# Balanced_Car.net
KiCad netlist of a schematic drawn in EasyEDA Pro
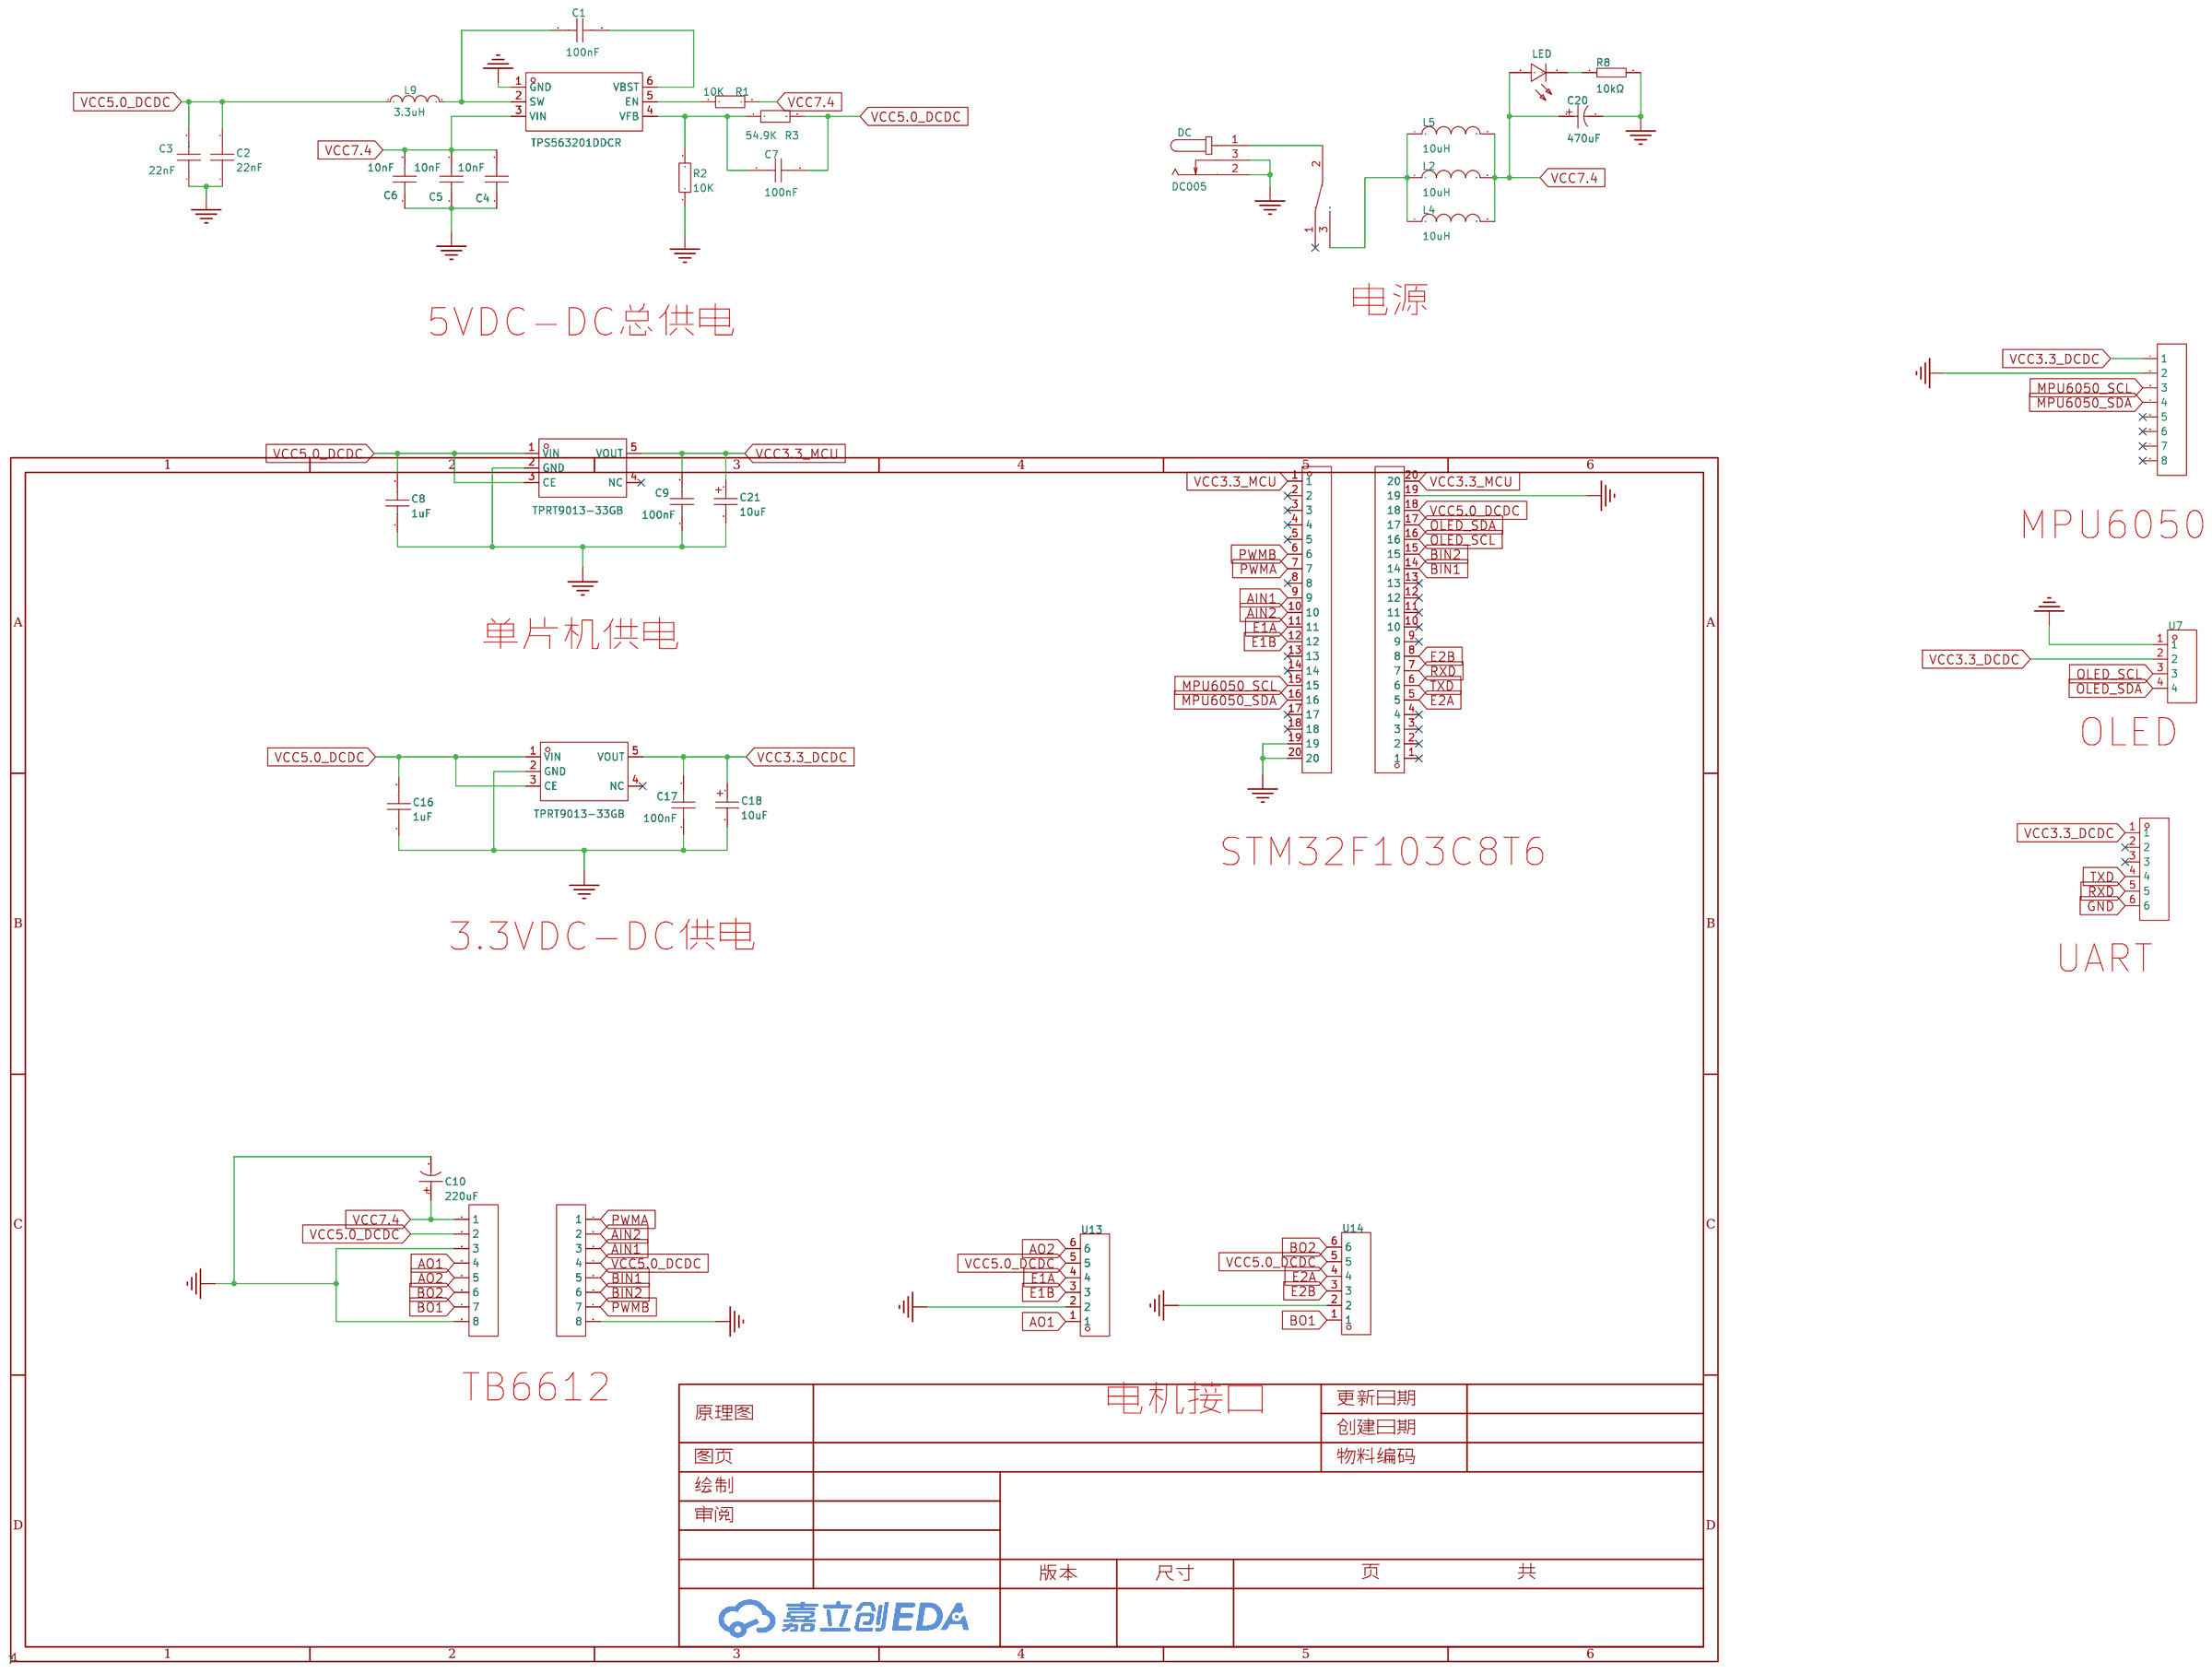
[diagram p0: schematic sheet]

(export (version "E")
  (design (tool "Eeschema 10.0.6"))
  (components
    (comp (ref "C1")
      (value "100nF")
      (footprint "easyedapro:C0603")
      (libsource (lib "easyedapro") (part "capacitance"))
    )
    (comp (ref "C2")
      (value "22nF")
      (footprint "easyedapro:C0603")
      (libsource (lib "easyedapro") (part "capacitance"))
    )
    (comp (ref "C3")
      (value "22nF")
      (footprint "easyedapro:C0603")
      (libsource (lib "easyedapro") (part "capacitance"))
    )
    (comp (ref "C4")
      (value "10nF")
      (footprint "easyedapro:C0603")
      (libsource (lib "easyedapro") (part "capacitance"))
    )
    (comp (ref "C5")
      (value "10nF")
      (footprint "easyedapro:C0603")
      (libsource (lib "easyedapro") (part "capacitance"))
    )
    (comp (ref "C6")
      (value "10nF")
      (footprint "easyedapro:C0603")
      (libsource (lib "easyedapro") (part "capacitance"))
    )
    (comp (ref "C7")
      (value "100nF")
      (footprint "easyedapro:C0603")
      (libsource (lib "easyedapro") (part "capacitance"))
    )
    (comp (ref "C8")
      (value "1uF")
      (footprint "easyedapro:C0603")
      (libsource (lib "easyedapro") (part "capacitance"))
    )
    (comp (ref "C9")
      (value "100nF")
      (footprint "easyedapro:C0603")
      (libsource (lib "easyedapro") (part "capacitance"))
    )
    (comp (ref "C10")
      (value "220uF")
      (footprint "easyedapro:CAP-TH_BD6.3-P2.50-D1.0-FD")
      (description "容值:220uF;精度:±20%;额定电压:16V;纹波电流:-;等效串联电阻:-;")
      (fields
        (field (name "Manufacturer Part") "KS227M016E07RR0VH2FP0")
        (field (name "Manufacturer") "CX(承兴)")
      )
      (libsource (lib "easyedapro") (part "220uF 16V 6.3*7"))
    )
    (comp (ref "C16")
      (value "1uF")
      (footprint "easyedapro:C0603")
      (libsource (lib "easyedapro") (part "capacitance"))
    )
    (comp (ref "C17")
      (value "100nF")
      (footprint "easyedapro:C0603")
      (libsource (lib "easyedapro") (part "capacitance"))
    )
    (comp (ref "C18")
      (value "10uF")
      (footprint "easyedapro:CAP-SMD_L3.2-W1.6-RD-C7171")
      (description "容值:10uF;精度:±10%;额定电压:16V;等效串联电阻:3Ω@100kHz;")
      (fields (field (name "Manufacturer Part") "TAJA106K016RNJ") (field (name "Manufacturer") "Kyocera AVX"))
      (libsource (lib "easyedapro") (part "TAJA106K016RNJ"))
    )
    (comp (ref "C20")
      (value "470uF")
      (footprint "easyedapro:CAP-TH_BD8.0-P3.50-D0.6-FD")
      (description "容值:470uF;精度:±20%;额定电压:25V;")
      (fields
        (field (name "Manufacturer Part") "KM477M025F12RR0VH2FP0")
        (field (name "Manufacturer") "CX(承兴)")
      )
      (libsource (lib "easyedapro") (part "470uF 25V 8*12"))
    )
    (comp (ref "C21")
      (value "10uF")
      (footprint "easyedapro:CAP-SMD_L3.2-W1.6-RD-C7171")
      (description "容值:10uF;精度:±10%;额定电压:16V;等效串联电阻:3Ω@100kHz;")
      (fields (field (name "Manufacturer Part") "TAJA106K016RNJ") (field (name "Manufacturer") "Kyocera AVX"))
      (libsource (lib "easyedapro") (part "TAJA106K016RNJ"))
    )
    (comp (ref "DC")
      (value "DC005")
      (footprint "easyedapro:DC-IN-TH_DC005")
      (description "连接器类型:DC电源插座;安装方式:弯插;触点内径:2mm;触点外径:6.3mm;额定电流:500mA;额定电压:30V;工作温度范围:-40°C~+55°C;")
      (fields (field (name "Manufacturer") "SHOU HAN(首韩)"))
      (libsource (lib "easyedapro") (part "DC005_C431533"))
    )
    (comp (ref "H7")
      (value "~")
      (footprint "easyedapro:HDR-TH_8P-P2.54-V-F-1")
      (libsource (lib "easyedapro") (part "Header-Female-2.54_1x8"))
    )
    (comp (ref "H8")
      (value "PM254V-11-06-H85")
      (footprint "easyedapro:HDR-TH_6P-P2.54-V-F")
      (fields (field (name "Manufacturer") "XFCN(兴飞)"))
      (libsource (lib "easyedapro") (part "PM254V-11-06-H85"))
    )
    (comp (ref "L2")
      (value "10uH")
      (fields
        (field (name "Manufacturer Part") "MGFL2012F100MT-LF")
        (field (name "Manufacturer") "microgate(麦捷科技)")
      )
      (libsource (lib "easyedapro") (part "IND"))
    )
    (comp (ref "L4")
      (value "10uH")
      (fields
        (field (name "Manufacturer Part") "MGFL2012F100MT-LF")
        (field (name "Manufacturer") "microgate(麦捷科技)")
      )
      (libsource (lib "easyedapro") (part "IND"))
    )
    (comp (ref "L5")
      (value "10uH")
      (fields
        (field (name "Manufacturer Part") "MGFL2012F100MT-LF")
        (field (name "Manufacturer") "microgate(麦捷科技)")
      )
      (libsource (lib "easyedapro") (part "IND"))
    )
    (comp (ref "L9")
      (value "3.3uH")
      (footprint "easyedapro:IND-SMD_L7.0-W6.6")
      (description "电感值:3.3uH;精度:±20%;额定电流:8.5A;饱和电流(Isat):9.5A;类型:一体成型电感;")
      (fields (field (name "Manufacturer Part") "FXL0630-3R3-M") (field (name "Manufacturer") "cjiang(长江微电)"))
      (libsource (lib "easyedapro") (part "FXL0630-3R3-M"))
    )
    (comp (ref "LED")
      (value "NCD0603G1")
      (footprint "easyedapro:LED0603-RD")
      (fields (field (name "Manufacturer") "国星光电"))
      (libsource (lib "easyedapro") (part "FC-D1608UGK-520D10"))
    )
    (comp (ref "R1") (value "10K") (footprint "easyedapro:R0603") (libsource (lib "easyedapro") (part "电阻")))
    (comp (ref "R2") (value "10K") (footprint "easyedapro:R0603") (libsource (lib "easyedapro") (part "电阻")))
    (comp (ref "R3")
      (value "54.9K")
      (footprint "easyedapro:R0603")
      (libsource (lib "easyedapro") (part "电阻"))
    )
    (comp (ref "R8")
      (value "10kΩ")
      (fields
        (field (name "Manufacturer Part") "0805W8F1501T5E")
        (field (name "Manufacturer") "UNI-ROYAL(厚声)")
      )
      (libsource (lib "easyedapro") (part "RES"))
    )
    (comp (ref "U1")
      (value "TPS563201DDCR")
      (footprint "easyedapro:SOT-23-6_L2.9-W1.6-P0.95-LS2.8-BR")
      (description "功能类型:降压型;输出类型:可调;输入电压:4.5V~17V;输出电压:768mV~7V;输出电流:3A;")
      (fields (field (name "Manufacturer") "TI(德州仪器)"))
      (libsource (lib "easyedapro") (part "TPS563201DDCR"))
    )
    (comp (ref "U2")
      (value "~")
      (footprint "easyedapro:HDR-TH_8P-P2.54-V-F-1")
      (libsource (lib "easyedapro") (part "Header-Female-2.54_1x8"))
    )
    (comp (ref "U3")
      (value "TPRT9013-33GB")
      (footprint "easyedapro:SOT-23-5_L3.0-W1.7-P0.95-LS2.8-BL")
      (description "输出类型:-;")
      (fields (field (name "Manufacturer") "TECH PUBLIC(台舟)"))
      (libsource (lib "easyedapro") (part "TPRT9013-33GB"))
    )
    (comp (ref "U5")
      (value "~")
      (footprint "easyedapro:HDR-TH_8P-P2.54-V-F-1")
      (libsource (lib "easyedapro") (part "Header-Female-2.54_1x8"))
    )
    (comp (ref "U6")
      (value "TPRT9013-33GB")
      (footprint "easyedapro:SOT-23-5_L3.0-W1.7-P0.95-LS2.8-BL")
      (description "输出类型:-;")
      (fields (field (name "Manufacturer") "TECH PUBLIC(台舟)"))
      (libsource (lib "easyedapro") (part "TPRT9013-33GB"))
    )
    (comp (ref "U7")
      (value "PM2.54-1*4")
      (footprint "easyedapro:HDR-TH_4P-P2.54-V-F")
      (fields (field (name "Manufacturer") "ZHOURI(洲日)"))
      (libsource (lib "easyedapro") (part "PM2.54-1*4"))
    )
    (comp (ref "U11")
      (value "KH-2.54FH-1X20P-H8.5")
      (footprint "easyedapro:HDR-TH_20P-P2.54-V-F-2")
      (fields (field (name "Manufacturer") "kinghelm(金航标)"))
      (libsource (lib "easyedapro") (part "KH-2.54FH-1X20P-H8.5"))
    )
    (comp (ref "U12")
      (value "KH-2.54FH-1X20P-H8.5")
      (footprint "easyedapro:HDR-TH_20P-P2.54-V-F-2")
      (fields (field (name "Manufacturer") "kinghelm(金航标)"))
      (libsource (lib "easyedapro") (part "KH-2.54FH-1X20P-H8.5"))
    )
    (comp (ref "U13")
      (value "X8821WR-06S-N0SN")
      (footprint "easyedapro:CONN-TH_6P-P2.50_X8821WR-06S-N2SN")
      (description "插针结构:1x6P;间距:2.5mm;安装方式:弯插;参考系列:XH;总PIN数:6P;排数:1;每排PIN数:6;行距:-;额定电流:3A;触头材质:黄铜;触头镀层:锡;工作温度范围:-;")
      (fields (field (name "Manufacturer") "XKB Connection(中国星坤)"))
      (libsource (lib "easyedapro") (part "X8821WR-06S-N0SN"))
    )
    (comp (ref "U14")
      (value "X8821WR-06S-N0SN")
      (footprint "easyedapro:CONN-TH_6P-P2.50_X8821WR-06S-N2SN")
      (description "插针结构:1x6P;间距:2.5mm;安装方式:弯插;参考系列:XH;总PIN数:6P;排数:1;每排PIN数:6;行距:-;额定电流:3A;触头材质:黄铜;触头镀层:锡;工作温度范围:-;")
      (fields (field (name "Manufacturer") "XKB Connection(中国星坤)"))
      (libsource (lib "easyedapro") (part "X8821WR-06S-N0SN"))
    )
    (comp (ref "U16")
      (value "MT-0-102-A101-M200-RS")
      (footprint "easyedapro:SW-TH_MT-0-103-A101-M200-RS")
      (description "电路结构:单刀双掷;机械寿命:-;额定电流:5A;额定电压(AC):125V;安装方式:直插;")
      (fields (field (name "Manufacturer") "YUEN FUNG(源丰)"))
      (libsource (lib "easyedapro") (part "MT-0-102-A101-M200-RS+PJ"))
    )
  )
  (nets
    (net (code "1") (name "AIN1") (class "Default")
      (node (ref "U11") (pin "9") (pinfunction "9_9") (pintype "unspecified"))
      (node (ref "U2") (pin "3") (pinfunction "3_3") (pintype "input"))
    )
    (net (code "2") (name "AIN2") (class "Default")
      (node (ref "U11") (pin "10") (pinfunction "10_10") (pintype "unspecified"))
      (node (ref "U2") (pin "2") (pinfunction "2_2") (pintype "input"))
    )
    (net (code "3") (name "AO1") (class "Default")
      (node (ref "U13") (pin "1") (pinfunction "1_1") (pintype "unspecified"))
      (node (ref "U5") (pin "4") (pinfunction "4_4") (pintype "input"))
    )
    (net (code "4") (name "AO2") (class "Default")
      (node (ref "U13") (pin "6") (pinfunction "6_6") (pintype "unspecified"))
      (node (ref "U5") (pin "5") (pinfunction "5_5") (pintype "input"))
    )
    (net (code "5") (name "BIN1") (class "Default")
      (node (ref "U12") (pin "14") (pinfunction "14_14") (pintype "unspecified"))
      (node (ref "U2") (pin "5") (pinfunction "5_5") (pintype "input"))
    )
    (net (code "6") (name "BIN2") (class "Default")
      (node (ref "U12") (pin "15") (pinfunction "15_15") (pintype "unspecified"))
      (node (ref "U2") (pin "6") (pinfunction "6_6") (pintype "input"))
    )
    (net (code "7") (name "BO1") (class "Default")
      (node (ref "U14") (pin "1") (pinfunction "1_1") (pintype "unspecified"))
      (node (ref "U5") (pin "7") (pinfunction "7_7") (pintype "input"))
    )
    (net (code "8") (name "BO2") (class "Default")
      (node (ref "U14") (pin "6") (pinfunction "6_6") (pintype "unspecified"))
      (node (ref "U5") (pin "6") (pinfunction "6_6") (pintype "input"))
    )
    (net (code "9") (name "E1A") (class "Default")
      (node (ref "U11") (pin "11") (pinfunction "11_11") (pintype "unspecified"))
      (node (ref "U13") (pin "4") (pinfunction "4_4") (pintype "unspecified"))
    )
    (net (code "10") (name "E1B") (class "Default")
      (node (ref "U11") (pin "12") (pinfunction "12_12") (pintype "unspecified"))
      (node (ref "U13") (pin "3") (pinfunction "3_3") (pintype "unspecified"))
    )
    (net (code "11") (name "E2A") (class "Default")
      (node (ref "U12") (pin "5") (pinfunction "5_5") (pintype "unspecified"))
      (node (ref "U14") (pin "4") (pinfunction "4_4") (pintype "unspecified"))
    )
    (net (code "12") (name "E2B") (class "Default")
      (node (ref "U12") (pin "8") (pinfunction "8_8") (pintype "unspecified"))
      (node (ref "U14") (pin "3") (pinfunction "3_3") (pintype "unspecified"))
    )
    (net (code "13") (name "GND") (class "Default")
      (node (ref "C10") (pin "2") (pinfunction "2_2") (pintype "input"))
      (node (ref "C16") (pin "1") (pinfunction "1_1") (pintype "input"))
      (node (ref "C17") (pin "1") (pinfunction "1_1") (pintype "input"))
      (node (ref "C18") (pin "2") (pinfunction "2_2") (pintype "input"))
      (node (ref "C2") (pin "1") (pinfunction "1_1") (pintype "input"))
      (node (ref "C20") (pin "2") (pinfunction "2_2") (pintype "input"))
      (node (ref "C21") (pin "2") (pinfunction "2_2") (pintype "input"))
      (node (ref "C3") (pin "1") (pinfunction "1_1") (pintype "input"))
      (node (ref "C4") (pin "1") (pinfunction "1_1") (pintype "input"))
      (node (ref "C5") (pin "1") (pinfunction "1_1") (pintype "input"))
      (node (ref "C6") (pin "1") (pinfunction "1_1") (pintype "input"))
      (node (ref "C8") (pin "1") (pinfunction "1_1") (pintype "input"))
      (node (ref "C9") (pin "1") (pinfunction "1_1") (pintype "input"))
      (node (ref "DC") (pin "2") (pinfunction "2_2") (pintype "unspecified"))
      (node (ref "DC") (pin "3") (pinfunction "3_3") (pintype "unspecified"))
      (node (ref "H7") (pin "2") (pinfunction "2_2") (pintype "input"))
      (node (ref "H8") (pin "6") (pinfunction "6_6") (pintype "unspecified"))
      (node (ref "R2") (pin "1") (pinfunction "1_1") (pintype "input"))
      (node (ref "R8") (pin "2") (pintype "unspecified"))
      (node (ref "U1") (pin "1") (pinfunction "GND_1") (pintype "unspecified"))
      (node (ref "U11") (pin "19") (pinfunction "19_19") (pintype "unspecified"))
      (node (ref "U11") (pin "20") (pinfunction "20_20") (pintype "unspecified"))
      (node (ref "U12") (pin "19") (pinfunction "19_19") (pintype "unspecified"))
      (node (ref "U13") (pin "2") (pinfunction "2_2") (pintype "unspecified"))
      (node (ref "U14") (pin "2") (pinfunction "2_2") (pintype "unspecified"))
      (node (ref "U2") (pin "8") (pinfunction "8_8") (pintype "input"))
      (node (ref "U3") (pin "2") (pinfunction "GND_2") (pintype "unspecified"))
      (node (ref "U5") (pin "3") (pinfunction "3_3") (pintype "input"))
      (node (ref "U5") (pin "8") (pinfunction "8_8") (pintype "input"))
      (node (ref "U6") (pin "2") (pinfunction "GND_2") (pintype "unspecified"))
      (node (ref "U7") (pin "1") (pinfunction "1_1") (pintype "unspecified"))
    )
    (net (code "14") (name "MPU6050_SCL") (class "Default")
      (node (ref "H7") (pin "3") (pinfunction "3_3") (pintype "input"))
      (node (ref "U11") (pin "15") (pinfunction "15_15") (pintype "unspecified"))
    )
    (net (code "15") (name "MPU6050_SDA") (class "Default")
      (node (ref "H7") (pin "4") (pinfunction "4_4") (pintype "input"))
      (node (ref "U11") (pin "16") (pinfunction "16_16") (pintype "unspecified"))
    )
    (net (code "16") (name "Net-(DC-Pad1)") (class "Default")
      (node (ref "DC") (pin "1") (pinfunction "1_1") (pintype "unspecified"))
      (node (ref "U16") (pin "2") (pinfunction "2_2") (pintype "unspecified"))
    )
    (net (code "17") (name "Net-(L2-Pad1)") (class "Default")
      (node (ref "L2") (pin "1") (pinfunction "1_1") (pintype "unspecified"))
      (node (ref "L4") (pin "1") (pinfunction "1_1") (pintype "unspecified"))
      (node (ref "L5") (pin "1") (pinfunction "1_1") (pintype "unspecified"))
      (node (ref "U16") (pin "3") (pinfunction "3_3") (pintype "unspecified"))
    )
    (net (code "18") (name "Net-(LED-K)") (class "Default")
      (node (ref "LED") (pin "1") (pinfunction "K_1") (pintype "input"))
      (node (ref "R8") (pin "1") (pintype "unspecified"))
    )
    (net (code "19") (name "Net-(U1-EN)") (class "Default")
      (node (ref "R1") (pin "1") (pinfunction "1_1") (pintype "input"))
      (node (ref "U1") (pin "5") (pinfunction "EN_5") (pintype "unspecified"))
    )
    (net (code "20") (name "Net-(U1-SW)") (class "Default")
      (node (ref "C1") (pin "1") (pinfunction "1_1") (pintype "input"))
      (node (ref "L9") (pin "2") (pinfunction "2_2") (pintype "unspecified"))
      (node (ref "U1") (pin "2") (pinfunction "SW_2") (pintype "unspecified"))
    )
    (net (code "21") (name "Net-(U1-VBST)") (class "Default")
      (node (ref "C1") (pin "2") (pinfunction "2_2") (pintype "input"))
      (node (ref "U1") (pin "6") (pinfunction "VBST_6") (pintype "unspecified"))
    )
    (net (code "22") (name "Net-(U1-VFB)") (class "Default")
      (node (ref "C7") (pin "1") (pinfunction "1_1") (pintype "input"))
      (node (ref "R2") (pin "2") (pinfunction "2_2") (pintype "input"))
      (node (ref "R3") (pin "1") (pinfunction "1_1") (pintype "input"))
      (node (ref "U1") (pin "4") (pinfunction "VFB_4") (pintype "unspecified"))
    )
    (net (code "23") (name "OLED_SCL") (class "Default")
      (node (ref "U12") (pin "16") (pinfunction "16_16") (pintype "unspecified"))
      (node (ref "U7") (pin "3") (pinfunction "3_3") (pintype "unspecified"))
    )
    (net (code "24") (name "OLED_SDA") (class "Default")
      (node (ref "U12") (pin "17") (pinfunction "17_17") (pintype "unspecified"))
      (node (ref "U7") (pin "4") (pinfunction "4_4") (pintype "unspecified"))
    )
    (net (code "25") (name "PWMA") (class "Default")
      (node (ref "U11") (pin "7") (pinfunction "7_7") (pintype "unspecified"))
      (node (ref "U2") (pin "1") (pinfunction "1_1") (pintype "input"))
    )
    (net (code "26") (name "PWMB") (class "Default")
      (node (ref "U11") (pin "6") (pinfunction "6_6") (pintype "unspecified"))
      (node (ref "U2") (pin "7") (pinfunction "7_7") (pintype "input"))
    )
    (net (code "27") (name "RXD") (class "Default")
      (node (ref "H8") (pin "5") (pinfunction "5_5") (pintype "unspecified"))
      (node (ref "U12") (pin "7") (pinfunction "7_7") (pintype "unspecified"))
    )
    (net (code "28") (name "TXD") (class "Default")
      (node (ref "H8") (pin "4") (pinfunction "4_4") (pintype "unspecified"))
      (node (ref "U12") (pin "6") (pinfunction "6_6") (pintype "unspecified"))
    )
    (net (code "29") (name "VCC3.3_DCDC") (class "Default")
      (node (ref "C17") (pin "2") (pinfunction "2_2") (pintype "input"))
      (node (ref "C18") (pin "1") (pinfunction "1_1") (pintype "input"))
      (node (ref "H7") (pin "1") (pinfunction "1_1") (pintype "input"))
      (node (ref "H8") (pin "1") (pinfunction "1_1") (pintype "unspecified"))
      (node (ref "U6") (pin "5") (pinfunction "VOUT_5") (pintype "unspecified"))
      (node (ref "U7") (pin "2") (pinfunction "2_2") (pintype "unspecified"))
    )
    (net (code "30") (name "VCC3.3_MCU") (class "Default")
      (node (ref "C21") (pin "1") (pinfunction "1_1") (pintype "input"))
      (node (ref "C9") (pin "2") (pinfunction "2_2") (pintype "input"))
      (node (ref "U11") (pin "1") (pinfunction "1_1") (pintype "unspecified"))
      (node (ref "U12") (pin "20") (pinfunction "20_20") (pintype "unspecified"))
      (node (ref "U3") (pin "5") (pinfunction "VOUT_5") (pintype "unspecified"))
    )
    (net (code "31") (name "VCC5.0_DCDC") (class "Default")
      (node (ref "C16") (pin "2") (pinfunction "2_2") (pintype "input"))
      (node (ref "C2") (pin "2") (pinfunction "2_2") (pintype "input"))
      (node (ref "C3") (pin "2") (pinfunction "2_2") (pintype "input"))
      (node (ref "C7") (pin "2") (pinfunction "2_2") (pintype "input"))
      (node (ref "C8") (pin "2") (pinfunction "2_2") (pintype "input"))
      (node (ref "L9") (pin "1") (pinfunction "1_1") (pintype "unspecified"))
      (node (ref "R3") (pin "2") (pinfunction "2_2") (pintype "input"))
      (node (ref "U12") (pin "18") (pinfunction "18_18") (pintype "unspecified"))
      (node (ref "U13") (pin "5") (pinfunction "5_5") (pintype "unspecified"))
      (node (ref "U14") (pin "5") (pinfunction "5_5") (pintype "unspecified"))
      (node (ref "U2") (pin "4") (pinfunction "4_4") (pintype "input"))
      (node (ref "U3") (pin "1") (pinfunction "VIN_1") (pintype "unspecified"))
      (node (ref "U3") (pin "3") (pinfunction "CE_3") (pintype "unspecified"))
      (node (ref "U5") (pin "2") (pinfunction "2_2") (pintype "input"))
      (node (ref "U6") (pin "1") (pinfunction "VIN_1") (pintype "unspecified"))
      (node (ref "U6") (pin "3") (pinfunction "CE_3") (pintype "unspecified"))
    )
    (net (code "32") (name "VCC7.4") (class "Default")
      (node (ref "C10") (pin "1") (pinfunction "1_1") (pintype "input"))
      (node (ref "C20") (pin "1") (pinfunction "1_1") (pintype "input"))
      (node (ref "C4") (pin "2") (pinfunction "2_2") (pintype "input"))
      (node (ref "C5") (pin "2") (pinfunction "2_2") (pintype "input"))
      (node (ref "C6") (pin "2") (pinfunction "2_2") (pintype "input"))
      (node (ref "L2") (pin "2") (pinfunction "2_2") (pintype "unspecified"))
      (node (ref "L4") (pin "2") (pinfunction "2_2") (pintype "unspecified"))
      (node (ref "L5") (pin "2") (pinfunction "2_2") (pintype "unspecified"))
      (node (ref "LED") (pin "2") (pinfunction "A_2") (pintype "input"))
      (node (ref "R1") (pin "2") (pinfunction "2_2") (pintype "input"))
      (node (ref "U1") (pin "3") (pinfunction "VIN_3") (pintype "unspecified"))
      (node (ref "U5") (pin "1") (pinfunction "1_1") (pintype "input"))
    )
    (net (code "33") (name "unconnected-(H7-Pad5)") (class "Default")
      (node (ref "H7") (pin "5") (pinfunction "5_5") (pintype "input+no_connect"))
    )
    (net (code "34") (name "unconnected-(H7-Pad6)") (class "Default")
      (node (ref "H7") (pin "6") (pinfunction "6_6") (pintype "input+no_connect"))
    )
    (net (code "35") (name "unconnected-(H7-Pad7)") (class "Default")
      (node (ref "H7") (pin "7") (pinfunction "7_7") (pintype "input+no_connect"))
    )
    (net (code "36") (name "unconnected-(H7-Pad8)") (class "Default")
      (node (ref "H7") (pin "8") (pinfunction "8_8") (pintype "input+no_connect"))
    )
    (net (code "37") (name "unconnected-(H8-Pad2)") (class "Default")
      (node (ref "H8") (pin "2") (pinfunction "2_2") (pintype "unspecified+no_connect"))
    )
    (net (code "38") (name "unconnected-(H8-Pad3)") (class "Default")
      (node (ref "H8") (pin "3") (pinfunction "3_3") (pintype "unspecified+no_connect"))
    )
    (net (code "39") (name "unconnected-(U3-NC-Pad4)") (class "Default")
      (node (ref "U3") (pin "4") (pinfunction "NC_4") (pintype "unspecified+no_connect"))
    )
    (net (code "40") (name "unconnected-(U6-NC-Pad4)") (class "Default")
      (node (ref "U6") (pin "4") (pinfunction "NC_4") (pintype "unspecified+no_connect"))
    )
    (net (code "41") (name "unconnected-(U11-Pad2)") (class "Default")
      (node (ref "U11") (pin "2") (pinfunction "2_2") (pintype "unspecified+no_connect"))
    )
    (net (code "42") (name "unconnected-(U11-Pad3)") (class "Default")
      (node (ref "U11") (pin "3") (pinfunction "3_3") (pintype "unspecified+no_connect"))
    )
    (net (code "43") (name "unconnected-(U11-Pad4)") (class "Default")
      (node (ref "U11") (pin "4") (pinfunction "4_4") (pintype "unspecified+no_connect"))
    )
    (net (code "44") (name "unconnected-(U11-Pad5)") (class "Default")
      (node (ref "U11") (pin "5") (pinfunction "5_5") (pintype "unspecified+no_connect"))
    )
    (net (code "45") (name "unconnected-(U11-Pad8)") (class "Default")
      (node (ref "U11") (pin "8") (pinfunction "8_8") (pintype "unspecified+no_connect"))
    )
    (net (code "46") (name "unconnected-(U11-Pad13)") (class "Default")
      (node (ref "U11") (pin "13") (pinfunction "13_13") (pintype "unspecified+no_connect"))
    )
    (net (code "47") (name "unconnected-(U11-Pad14)") (class "Default")
      (node (ref "U11") (pin "14") (pinfunction "14_14") (pintype "unspecified+no_connect"))
    )
    (net (code "48") (name "unconnected-(U11-Pad17)") (class "Default")
      (node (ref "U11") (pin "17") (pinfunction "17_17") (pintype "unspecified+no_connect"))
    )
    (net (code "49") (name "unconnected-(U11-Pad18)") (class "Default")
      (node (ref "U11") (pin "18") (pinfunction "18_18") (pintype "unspecified+no_connect"))
    )
    (net (code "50") (name "unconnected-(U12-Pad1)") (class "Default")
      (node (ref "U12") (pin "1") (pinfunction "1_1") (pintype "unspecified+no_connect"))
    )
    (net (code "51") (name "unconnected-(U12-Pad2)") (class "Default")
      (node (ref "U12") (pin "2") (pinfunction "2_2") (pintype "unspecified+no_connect"))
    )
    (net (code "52") (name "unconnected-(U12-Pad3)") (class "Default")
      (node (ref "U12") (pin "3") (pinfunction "3_3") (pintype "unspecified+no_connect"))
    )
    (net (code "53") (name "unconnected-(U12-Pad4)") (class "Default")
      (node (ref "U12") (pin "4") (pinfunction "4_4") (pintype "unspecified+no_connect"))
    )
    (net (code "54") (name "unconnected-(U12-Pad9)") (class "Default")
      (node (ref "U12") (pin "9") (pinfunction "9_9") (pintype "unspecified+no_connect"))
    )
    (net (code "55") (name "unconnected-(U12-Pad10)") (class "Default")
      (node (ref "U12") (pin "10") (pinfunction "10_10") (pintype "unspecified+no_connect"))
    )
    (net (code "56") (name "unconnected-(U12-Pad11)") (class "Default")
      (node (ref "U12") (pin "11") (pinfunction "11_11") (pintype "unspecified+no_connect"))
    )
    (net (code "57") (name "unconnected-(U12-Pad12)") (class "Default")
      (node (ref "U12") (pin "12") (pinfunction "12_12") (pintype "unspecified+no_connect"))
    )
    (net (code "58") (name "unconnected-(U12-Pad13)") (class "Default")
      (node (ref "U12") (pin "13") (pinfunction "13_13") (pintype "unspecified+no_connect"))
    )
    (net (code "59") (name "unconnected-(U16-Pad1)") (class "Default")
      (node (ref "U16") (pin "1") (pinfunction "1_1") (pintype "unspecified+no_connect"))
    )
  )
)
